# Dicio_bkup.net
KiCad netlist of a schematic drawn in EAGLE
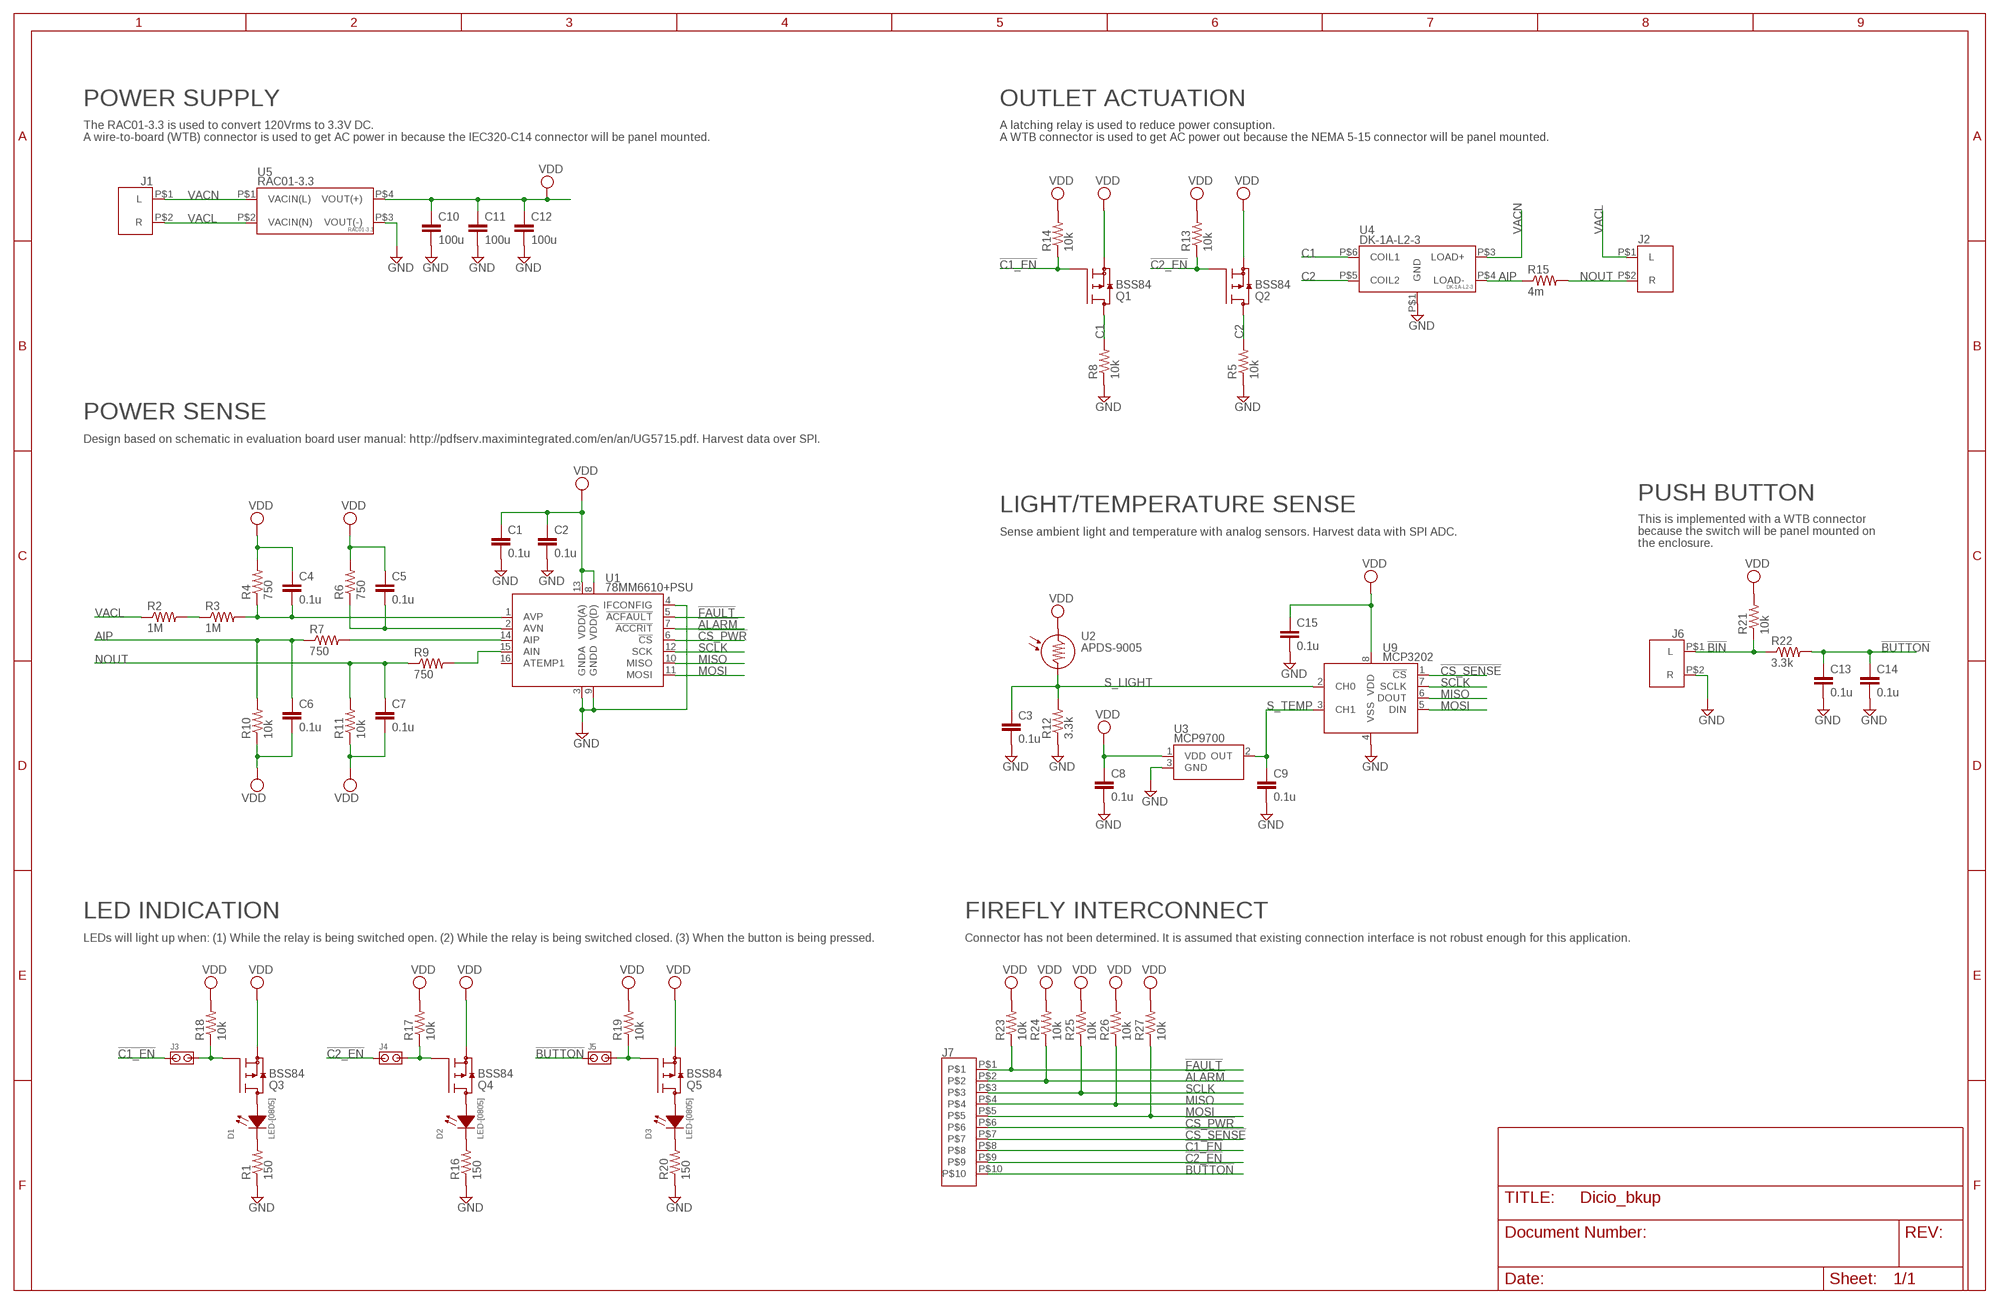
[diagram p0: schematic, sheet 1]

(export (version "E")
  (design (tool "Eeschema 10.0.6"))
  (components
    (comp (ref "C1")
      (value "0.1u")
      (footprint "eagle-import:C0805")
      (libsource (lib "eagle-import") (part "C-EUC0805"))
    )
    (comp (ref "C2")
      (value "0.1u")
      (footprint "eagle-import:C0805")
      (libsource (lib "eagle-import") (part "C-EUC0805"))
    )
    (comp (ref "C3")
      (value "0.1u")
      (footprint "eagle-import:C0805")
      (libsource (lib "eagle-import") (part "C-EUC0805"))
    )
    (comp (ref "C4")
      (value "0.1u")
      (footprint "eagle-import:C0805")
      (libsource (lib "eagle-import") (part "C-EUC0805"))
    )
    (comp (ref "C5")
      (value "0.1u")
      (footprint "eagle-import:C0805")
      (libsource (lib "eagle-import") (part "C-EUC0805"))
    )
    (comp (ref "C6")
      (value "0.1u")
      (footprint "eagle-import:C0805")
      (libsource (lib "eagle-import") (part "C-EUC0805"))
    )
    (comp (ref "C7")
      (value "0.1u")
      (footprint "eagle-import:C0805")
      (libsource (lib "eagle-import") (part "C-EUC0805"))
    )
    (comp (ref "C8")
      (value "0.1u")
      (footprint "eagle-import:C0805")
      (libsource (lib "eagle-import") (part "C-EUC0805"))
    )
    (comp (ref "C9")
      (value "0.1u")
      (footprint "eagle-import:C0805")
      (libsource (lib "eagle-import") (part "C-EUC0805"))
    )
    (comp (ref "C10")
      (value "100u")
      (footprint "eagle-import:C1206")
      (libsource (lib "eagle-import") (part "C-EUC1206"))
    )
    (comp (ref "C11")
      (value "100u")
      (footprint "eagle-import:C1206")
      (libsource (lib "eagle-import") (part "C-EUC1206"))
    )
    (comp (ref "C12")
      (value "100u")
      (footprint "eagle-import:C1206")
      (libsource (lib "eagle-import") (part "C-EUC1206"))
    )
    (comp (ref "C13")
      (value "0.1u")
      (footprint "eagle-import:C0805")
      (libsource (lib "eagle-import") (part "C-EUC0805"))
    )
    (comp (ref "C14")
      (value "0.1u")
      (footprint "eagle-import:C0805")
      (libsource (lib "eagle-import") (part "C-EUC0805"))
    )
    (comp (ref "C15")
      (value "0.1u")
      (footprint "eagle-import:C0805")
      (libsource (lib "eagle-import") (part "C-EUC0805"))
    )
    (comp (ref "D1")
      (value "LED-[0805]")
      (footprint "eagle-import:L0805")
      (libsource (lib "eagle-import") (part "LED-[0805]"))
    )
    (comp (ref "D2")
      (value "LED-[0805]")
      (footprint "eagle-import:L0805")
      (libsource (lib "eagle-import") (part "LED-[0805]"))
    )
    (comp (ref "D3")
      (value "LED-[0805]")
      (footprint "eagle-import:L0805")
      (libsource (lib "eagle-import") (part "LED-[0805]"))
    )
    (comp (ref "J1")
      (value "WTB-2")
      (footprint "eagle-import:[TERM][2][0.2]")
      (libsource (lib "eagle-import") (part "WTB-2"))
    )
    (comp (ref "J2")
      (value "WTB-2")
      (footprint "eagle-import:[TERM][2][0.2]")
      (libsource (lib "eagle-import") (part "WTB-2"))
    )
    (comp (ref "J3")
      (value "JMP2")
      (footprint "eagle-import:JMP2")
      (libsource (lib "eagle-import") (part "JMP2"))
    )
    (comp (ref "J4")
      (value "JMP2")
      (footprint "eagle-import:JMP2")
      (libsource (lib "eagle-import") (part "JMP2"))
    )
    (comp (ref "J5")
      (value "JMP2")
      (footprint "eagle-import:JMP2")
      (libsource (lib "eagle-import") (part "JMP2"))
    )
    (comp (ref "J6")
      (value "WTB-2")
      (footprint "eagle-import:[TERM][2][0.2]")
      (libsource (lib "eagle-import") (part "WTB-2"))
    )
    (comp (ref "J7")
      (value "TERM10")
      (footprint "eagle-import:TERM10")
      (libsource (lib "eagle-import") (part "TERM10"))
    )
    (comp (ref "Q1")
      (value "BSS84")
      (footprint "eagle-import:SOT23")
      (libsource (lib "eagle-import") (part "BSS84"))
    )
    (comp (ref "Q2")
      (value "BSS84")
      (footprint "eagle-import:SOT23")
      (libsource (lib "eagle-import") (part "BSS84"))
    )
    (comp (ref "Q3")
      (value "BSS84")
      (footprint "eagle-import:SOT23")
      (libsource (lib "eagle-import") (part "BSS84"))
    )
    (comp (ref "Q4")
      (value "BSS84")
      (footprint "eagle-import:SOT23")
      (libsource (lib "eagle-import") (part "BSS84"))
    )
    (comp (ref "Q5")
      (value "BSS84")
      (footprint "eagle-import:SOT23")
      (libsource (lib "eagle-import") (part "BSS84"))
    )
    (comp (ref "R1")
      (value "150")
      (footprint "eagle-import:R0805")
      (libsource (lib "eagle-import") (part "R-US_R0805"))
    )
    (comp (ref "R2")
      (value "1M")
      (footprint "eagle-import:R0805")
      (libsource (lib "eagle-import") (part "R-US_R0805"))
    )
    (comp (ref "R3")
      (value "1M")
      (footprint "eagle-import:R0805")
      (libsource (lib "eagle-import") (part "R-US_R0805"))
    )
    (comp (ref "R4")
      (value "750")
      (footprint "eagle-import:R0805")
      (libsource (lib "eagle-import") (part "R-US_R0805"))
    )
    (comp (ref "R5")
      (value "10k")
      (footprint "eagle-import:R0805")
      (libsource (lib "eagle-import") (part "R-US_R0805"))
    )
    (comp (ref "R6")
      (value "750")
      (footprint "eagle-import:R0805")
      (libsource (lib "eagle-import") (part "R-US_R0805"))
    )
    (comp (ref "R7")
      (value "750")
      (footprint "eagle-import:R0805")
      (libsource (lib "eagle-import") (part "R-US_R0805"))
    )
    (comp (ref "R8")
      (value "10k")
      (footprint "eagle-import:R0805")
      (libsource (lib "eagle-import") (part "R-US_R0805"))
    )
    (comp (ref "R9")
      (value "750")
      (footprint "eagle-import:R0805")
      (libsource (lib "eagle-import") (part "R-US_R0805"))
    )
    (comp (ref "R10")
      (value "10k")
      (footprint "eagle-import:R0805")
      (libsource (lib "eagle-import") (part "R-US_R0805"))
    )
    (comp (ref "R11")
      (value "10k")
      (footprint "eagle-import:R0805")
      (libsource (lib "eagle-import") (part "R-US_R0805"))
    )
    (comp (ref "R12")
      (value "3.3k")
      (footprint "eagle-import:R0805")
      (libsource (lib "eagle-import") (part "R-US_R0805"))
    )
    (comp (ref "R13")
      (value "10k")
      (footprint "eagle-import:R0805")
      (libsource (lib "eagle-import") (part "R-US_R0805"))
    )
    (comp (ref "R14")
      (value "10k")
      (footprint "eagle-import:R0805")
      (libsource (lib "eagle-import") (part "R-US_R0805"))
    )
    (comp (ref "R15")
      (value "4m")
      (footprint "eagle-import:R2512")
      (libsource (lib "eagle-import") (part "R-US_R2512"))
    )
    (comp (ref "R16")
      (value "150")
      (footprint "eagle-import:R0805")
      (libsource (lib "eagle-import") (part "R-US_R0805"))
    )
    (comp (ref "R17")
      (value "10k")
      (footprint "eagle-import:R0805")
      (libsource (lib "eagle-import") (part "R-US_R0805"))
    )
    (comp (ref "R18")
      (value "10k")
      (footprint "eagle-import:R0805")
      (libsource (lib "eagle-import") (part "R-US_R0805"))
    )
    (comp (ref "R19")
      (value "10k")
      (footprint "eagle-import:R0805")
      (libsource (lib "eagle-import") (part "R-US_R0805"))
    )
    (comp (ref "R20")
      (value "150")
      (footprint "eagle-import:R0805")
      (libsource (lib "eagle-import") (part "R-US_R0805"))
    )
    (comp (ref "R21")
      (value "10k")
      (footprint "eagle-import:R0805")
      (libsource (lib "eagle-import") (part "R-US_R0805"))
    )
    (comp (ref "R22")
      (value "3.3k")
      (footprint "eagle-import:R0805")
      (libsource (lib "eagle-import") (part "R-US_R0805"))
    )
    (comp (ref "R23")
      (value "10k")
      (footprint "eagle-import:R0805")
      (libsource (lib "eagle-import") (part "R-US_R0805"))
    )
    (comp (ref "R24")
      (value "10k")
      (footprint "eagle-import:R0805")
      (libsource (lib "eagle-import") (part "R-US_R0805"))
    )
    (comp (ref "R25")
      (value "10k")
      (footprint "eagle-import:R0805")
      (libsource (lib "eagle-import") (part "R-US_R0805"))
    )
    (comp (ref "R26")
      (value "10k")
      (footprint "eagle-import:R0805")
      (libsource (lib "eagle-import") (part "R-US_R0805"))
    )
    (comp (ref "R27")
      (value "10k")
      (footprint "eagle-import:R0805")
      (libsource (lib "eagle-import") (part "R-US_R0805"))
    )
    (comp (ref "U1")
      (value "78MM6610+PSU")
      (footprint "eagle-import:TSSOP16")
      (libsource (lib "eagle-import") (part "78MM6610+PSU"))
    )
    (comp (ref "U2")
      (value "APDS-9005")
      (footprint "eagle-import:APDS-9005")
      (libsource (lib "eagle-import") (part "APDS-9005"))
    )
    (comp (ref "U3")
      (value "MCP9700")
      (footprint "eagle-import:SOT23")
      (libsource (lib "eagle-import") (part "MCP9700"))
    )
    (comp (ref "U4")
      (value "DK-1A-L2-3")
      (footprint "eagle-import:DK-1A-L2-3")
      (libsource (lib "eagle-import") (part "DK-1A-L2-3"))
    )
    (comp (ref "U5")
      (value "RAC01-3.3")
      (footprint "eagle-import:RAC01-3.3")
      (libsource (lib "eagle-import") (part "RAC01-3.3"))
    )
    (comp (ref "U9")
      (value "MCP3202")
      (footprint "eagle-import:MSOP-8[MCP3202]")
      (libsource (lib "eagle-import") (part "MCP3202"))
    )
  )
  (nets
    (net (code "1") (name "/AIP") (class "Default")
      (node (ref "C6") (pin "1") (pinfunction "1_1") (pintype "passive"))
      (node (ref "R10") (pin "2") (pinfunction "2_2") (pintype "passive"))
      (node (ref "R15") (pin "1") (pinfunction "1_1") (pintype "passive"))
      (node (ref "R7") (pin "1") (pinfunction "1_1") (pintype "passive"))
      (node (ref "U4") (pin "P$4") (pinfunction "LOAD-_P$4") (pintype "bidirectional"))
    )
    (net (code "2") (name "/C1") (class "Default")
      (node (ref "Q1") (pin "3") (pinfunction "D_3") (pintype "bidirectional"))
      (node (ref "R8") (pin "2") (pinfunction "2_2") (pintype "passive"))
      (node (ref "U4") (pin "P$6") (pinfunction "COIL1_P$6") (pintype "bidirectional"))
    )
    (net (code "3") (name "/C2") (class "Default")
      (node (ref "Q2") (pin "3") (pinfunction "D_3") (pintype "bidirectional"))
      (node (ref "R5") (pin "2") (pinfunction "2_2") (pintype "passive"))
      (node (ref "U4") (pin "P$5") (pinfunction "COIL2_P$5") (pintype "bidirectional"))
    )
    (net (code "4") (name "/MISO") (class "Default")
      (node (ref "J7") (pin "P$4") (pinfunction "P$4_P$4") (pintype "bidirectional"))
      (node (ref "R26") (pin "1") (pinfunction "1_1") (pintype "passive"))
      (node (ref "U1") (pin "10") (pinfunction "MISO_10") (pintype "bidirectional"))
      (node (ref "U9") (pin "6") (pinfunction "DOUT_6") (pintype "bidirectional"))
    )
    (net (code "5") (name "/MOSI") (class "Default")
      (node (ref "J7") (pin "P$5") (pinfunction "P$5_P$5") (pintype "bidirectional"))
      (node (ref "R27") (pin "1") (pinfunction "1_1") (pintype "passive"))
      (node (ref "U1") (pin "11") (pinfunction "MOSI_11") (pintype "bidirectional"))
      (node (ref "U9") (pin "5") (pinfunction "DIN_5") (pintype "bidirectional"))
    )
    (net (code "6") (name "/NOUT") (class "Default")
      (node (ref "C7") (pin "1") (pinfunction "1_1") (pintype "passive"))
      (node (ref "J2") (pin "P$2") (pinfunction "R_P$2") (pintype "bidirectional"))
      (node (ref "R11") (pin "2") (pinfunction "2_2") (pintype "passive"))
      (node (ref "R15") (pin "2") (pinfunction "2_2") (pintype "passive"))
      (node (ref "R9") (pin "1") (pinfunction "1_1") (pintype "passive"))
    )
    (net (code "7") (name "/SCLK") (class "Default")
      (node (ref "J7") (pin "P$3") (pinfunction "P$3_P$3") (pintype "bidirectional"))
      (node (ref "R25") (pin "1") (pinfunction "1_1") (pintype "passive"))
      (node (ref "U1") (pin "12") (pinfunction "SCK_12") (pintype "bidirectional"))
      (node (ref "U9") (pin "7") (pinfunction "SCLK_7") (pintype "bidirectional"))
    )
    (net (code "8") (name "/S_LIGHT") (class "Default")
      (node (ref "C3") (pin "1") (pinfunction "1_1") (pintype "passive"))
      (node (ref "R12") (pin "2") (pinfunction "2_2") (pintype "passive"))
      (node (ref "U2") (pin "6") (pinfunction "ROUT_6") (pintype "bidirectional"))
      (node (ref "U9") (pin "2") (pinfunction "CH0_2") (pintype "bidirectional"))
    )
    (net (code "9") (name "/S_TEMP") (class "Default")
      (node (ref "C9") (pin "1") (pinfunction "1_1") (pintype "passive"))
      (node (ref "U3") (pin "2") (pinfunction "OUT_2") (pintype "bidirectional"))
      (node (ref "U9") (pin "3") (pinfunction "CH1_3") (pintype "bidirectional"))
    )
    (net (code "10") (name "/VACL") (class "Default")
      (node (ref "J1") (pin "P$2") (pinfunction "R_P$2") (pintype "bidirectional"))
      (node (ref "J2") (pin "P$1") (pinfunction "L_P$1") (pintype "bidirectional"))
      (node (ref "R2") (pin "1") (pinfunction "1_1") (pintype "passive"))
      (node (ref "U5") (pin "P$2") (pinfunction "VACIN(N)_P$2") (pintype "bidirectional"))
    )
    (net (code "11") (name "/VACN") (class "Default")
      (node (ref "J1") (pin "P$1") (pinfunction "L_P$1") (pintype "bidirectional"))
      (node (ref "U4") (pin "P$3") (pinfunction "LOAD+_P$3") (pintype "bidirectional"))
      (node (ref "U5") (pin "P$1") (pinfunction "VACIN(L)_P$1") (pintype "bidirectional"))
    )
    (net (code "12") (name "/~{ALARM}") (class "Default")
      (node (ref "J7") (pin "P$2") (pinfunction "P$2_P$2") (pintype "bidirectional"))
      (node (ref "R24") (pin "1") (pinfunction "1_1") (pintype "passive"))
      (node (ref "U1") (pin "7") (pinfunction "~{ACCRIT}_7") (pintype "bidirectional"))
    )
    (net (code "13") (name "/~{BIN}") (class "Default")
      (node (ref "J6") (pin "P$1") (pinfunction "L_P$1") (pintype "bidirectional"))
      (node (ref "R21") (pin "1") (pinfunction "1_1") (pintype "passive"))
      (node (ref "R22") (pin "1") (pinfunction "1_1") (pintype "passive"))
    )
    (net (code "14") (name "/~{BUTTON}") (class "Default")
      (node (ref "C13") (pin "1") (pinfunction "1_1") (pintype "passive"))
      (node (ref "C14") (pin "1") (pinfunction "1_1") (pintype "passive"))
      (node (ref "J5") (pin "P$2") (pinfunction "P$2_P$2") (pintype "bidirectional"))
      (node (ref "J7") (pin "P$10") (pinfunction "P$10_P$10") (pintype "bidirectional"))
      (node (ref "R22") (pin "2") (pinfunction "2_2") (pintype "passive"))
    )
    (net (code "15") (name "/~{C1_EN}") (class "Default")
      (node (ref "J3") (pin "P$2") (pinfunction "P$2_P$2") (pintype "bidirectional"))
      (node (ref "J7") (pin "P$8") (pinfunction "P$8_P$8") (pintype "bidirectional"))
      (node (ref "Q1") (pin "1") (pinfunction "G_1") (pintype "bidirectional"))
      (node (ref "R14") (pin "1") (pinfunction "1_1") (pintype "passive"))
    )
    (net (code "16") (name "/~{C2_EN}") (class "Default")
      (node (ref "J4") (pin "P$2") (pinfunction "P$2_P$2") (pintype "bidirectional"))
      (node (ref "J7") (pin "P$9") (pinfunction "P$9_P$9") (pintype "bidirectional"))
      (node (ref "Q2") (pin "1") (pinfunction "G_1") (pintype "bidirectional"))
      (node (ref "R13") (pin "1") (pinfunction "1_1") (pintype "passive"))
    )
    (net (code "17") (name "/~{CS_PWR}") (class "Default")
      (node (ref "J7") (pin "P$6") (pinfunction "P$6_P$6") (pintype "bidirectional"))
      (node (ref "U1") (pin "6") (pinfunction "~{CS}_6") (pintype "bidirectional"))
    )
    (net (code "18") (name "/~{CS_SENSE}") (class "Default")
      (node (ref "J7") (pin "P$7") (pinfunction "P$7_P$7") (pintype "bidirectional"))
      (node (ref "U9") (pin "1") (pinfunction "~{CS}_1") (pintype "bidirectional"))
    )
    (net (code "19") (name "/~{FAULT}") (class "Default")
      (node (ref "J7") (pin "P$1") (pinfunction "P$1_P$1") (pintype "bidirectional"))
      (node (ref "R23") (pin "1") (pinfunction "1_1") (pintype "passive"))
      (node (ref "U1") (pin "5") (pinfunction "~{ACFAULT}_5") (pintype "bidirectional"))
    )
    (net (code "20") (name "GND") (class "Default")
      (node (ref "C1") (pin "2") (pinfunction "2_2") (pintype "passive"))
      (node (ref "C10") (pin "2") (pinfunction "2_2") (pintype "passive"))
      (node (ref "C11") (pin "2") (pinfunction "2_2") (pintype "passive"))
      (node (ref "C12") (pin "2") (pinfunction "2_2") (pintype "passive"))
      (node (ref "C13") (pin "2") (pinfunction "2_2") (pintype "passive"))
      (node (ref "C14") (pin "2") (pinfunction "2_2") (pintype "passive"))
      (node (ref "C15") (pin "2") (pinfunction "2_2") (pintype "passive"))
      (node (ref "C2") (pin "2") (pinfunction "2_2") (pintype "passive"))
      (node (ref "C3") (pin "2") (pinfunction "2_2") (pintype "passive"))
      (node (ref "C8") (pin "2") (pinfunction "2_2") (pintype "passive"))
      (node (ref "C9") (pin "2") (pinfunction "2_2") (pintype "passive"))
      (node (ref "J6") (pin "P$2") (pinfunction "R_P$2") (pintype "bidirectional"))
      (node (ref "R1") (pin "1") (pinfunction "1_1") (pintype "passive"))
      (node (ref "R12") (pin "1") (pinfunction "1_1") (pintype "passive"))
      (node (ref "R16") (pin "1") (pinfunction "1_1") (pintype "passive"))
      (node (ref "R20") (pin "1") (pinfunction "1_1") (pintype "passive"))
      (node (ref "R5") (pin "1") (pinfunction "1_1") (pintype "passive"))
      (node (ref "R8") (pin "1") (pinfunction "1_1") (pintype "passive"))
      (node (ref "U1") (pin "3") (pinfunction "GNDA_3") (pintype "bidirectional"))
      (node (ref "U1") (pin "4") (pinfunction "IFCONFIG_4") (pintype "bidirectional"))
      (node (ref "U1") (pin "9") (pinfunction "GNDD_9") (pintype "bidirectional"))
      (node (ref "U3") (pin "3") (pinfunction "GND_3") (pintype "bidirectional"))
      (node (ref "U4") (pin "P$1") (pinfunction "GND_P$1") (pintype "bidirectional"))
      (node (ref "U5") (pin "P$3") (pinfunction "VOUT(-)_P$3") (pintype "bidirectional"))
      (node (ref "U9") (pin "4") (pinfunction "VSS_4") (pintype "bidirectional"))
    )
    (net (code "21") (name "Net-(D1-A)") (class "Default")
      (node (ref "D1") (pin "1") (pinfunction "A_1") (pintype "bidirectional"))
      (node (ref "Q3") (pin "3") (pinfunction "D_3") (pintype "bidirectional"))
    )
    (net (code "22") (name "Net-(D1-C)") (class "Default")
      (node (ref "D1") (pin "2") (pinfunction "C_2") (pintype "bidirectional"))
      (node (ref "R1") (pin "2") (pinfunction "2_2") (pintype "passive"))
    )
    (net (code "23") (name "Net-(D2-A)") (class "Default")
      (node (ref "D2") (pin "1") (pinfunction "A_1") (pintype "bidirectional"))
      (node (ref "Q4") (pin "3") (pinfunction "D_3") (pintype "bidirectional"))
    )
    (net (code "24") (name "Net-(D2-C)") (class "Default")
      (node (ref "D2") (pin "2") (pinfunction "C_2") (pintype "bidirectional"))
      (node (ref "R16") (pin "2") (pinfunction "2_2") (pintype "passive"))
    )
    (net (code "25") (name "Net-(D3-A)") (class "Default")
      (node (ref "D3") (pin "1") (pinfunction "A_1") (pintype "bidirectional"))
      (node (ref "Q5") (pin "3") (pinfunction "D_3") (pintype "bidirectional"))
    )
    (net (code "26") (name "Net-(D3-C)") (class "Default")
      (node (ref "D3") (pin "2") (pinfunction "C_2") (pintype "bidirectional"))
      (node (ref "R20") (pin "2") (pinfunction "2_2") (pintype "passive"))
    )
    (net (code "27") (name "Net-(J3-1)") (class "Default")
      (node (ref "J3") (pin "P$1") (pinfunction "1_P$1") (pintype "bidirectional"))
      (node (ref "Q3") (pin "1") (pinfunction "G_1") (pintype "bidirectional"))
      (node (ref "R18") (pin "1") (pinfunction "1_1") (pintype "passive"))
    )
    (net (code "28") (name "Net-(J4-1)") (class "Default")
      (node (ref "J4") (pin "P$1") (pinfunction "1_P$1") (pintype "bidirectional"))
      (node (ref "Q4") (pin "1") (pinfunction "G_1") (pintype "bidirectional"))
      (node (ref "R17") (pin "1") (pinfunction "1_1") (pintype "passive"))
    )
    (net (code "29") (name "Net-(J5-1)") (class "Default")
      (node (ref "J5") (pin "P$1") (pinfunction "1_P$1") (pintype "bidirectional"))
      (node (ref "Q5") (pin "1") (pinfunction "G_1") (pintype "bidirectional"))
      (node (ref "R19") (pin "1") (pinfunction "1_1") (pintype "passive"))
    )
    (net (code "30") (name "Net-(R2-Pad2)") (class "Default")
      (node (ref "R2") (pin "2") (pinfunction "2_2") (pintype "passive"))
      (node (ref "R3") (pin "1") (pinfunction "1_1") (pintype "passive"))
    )
    (net (code "31") (name "Net-(U1-AIN)") (class "Default")
      (node (ref "R9") (pin "2") (pinfunction "2_2") (pintype "passive"))
      (node (ref "U1") (pin "15") (pinfunction "AIN_15") (pintype "bidirectional"))
    )
    (net (code "32") (name "Net-(U1-AIP)") (class "Default")
      (node (ref "R7") (pin "2") (pinfunction "2_2") (pintype "passive"))
      (node (ref "U1") (pin "14") (pinfunction "AIP_14") (pintype "bidirectional"))
    )
    (net (code "33") (name "Net-(U1-AVN)") (class "Default")
      (node (ref "C5") (pin "2") (pinfunction "2_2") (pintype "passive"))
      (node (ref "R6") (pin "1") (pinfunction "1_1") (pintype "passive"))
      (node (ref "U1") (pin "2") (pinfunction "AVN_2") (pintype "bidirectional"))
    )
    (net (code "34") (name "Net-(U1-AVP)") (class "Default")
      (node (ref "C4") (pin "2") (pinfunction "2_2") (pintype "passive"))
      (node (ref "R3") (pin "2") (pinfunction "2_2") (pintype "passive"))
      (node (ref "R4") (pin "1") (pinfunction "1_1") (pintype "passive"))
      (node (ref "U1") (pin "1") (pinfunction "AVP_1") (pintype "bidirectional"))
    )
    (net (code "35") (name "VDD") (class "Default")
      (node (ref "C1") (pin "1") (pinfunction "1_1") (pintype "passive"))
      (node (ref "C10") (pin "1") (pinfunction "1_1") (pintype "passive"))
      (node (ref "C11") (pin "1") (pinfunction "1_1") (pintype "passive"))
      (node (ref "C12") (pin "1") (pinfunction "1_1") (pintype "passive"))
      (node (ref "C15") (pin "1") (pinfunction "1_1") (pintype "passive"))
      (node (ref "C2") (pin "1") (pinfunction "1_1") (pintype "passive"))
      (node (ref "C4") (pin "1") (pinfunction "1_1") (pintype "passive"))
      (node (ref "C5") (pin "1") (pinfunction "1_1") (pintype "passive"))
      (node (ref "C6") (pin "2") (pinfunction "2_2") (pintype "passive"))
      (node (ref "C7") (pin "2") (pinfunction "2_2") (pintype "passive"))
      (node (ref "C8") (pin "1") (pinfunction "1_1") (pintype "passive"))
      (node (ref "Q1") (pin "2") (pinfunction "S_2") (pintype "bidirectional"))
      (node (ref "Q2") (pin "2") (pinfunction "S_2") (pintype "bidirectional"))
      (node (ref "Q3") (pin "2") (pinfunction "S_2") (pintype "bidirectional"))
      (node (ref "Q4") (pin "2") (pinfunction "S_2") (pintype "bidirectional"))
      (node (ref "Q5") (pin "2") (pinfunction "S_2") (pintype "bidirectional"))
      (node (ref "R10") (pin "1") (pinfunction "1_1") (pintype "passive"))
      (node (ref "R11") (pin "1") (pinfunction "1_1") (pintype "passive"))
      (node (ref "R13") (pin "2") (pinfunction "2_2") (pintype "passive"))
      (node (ref "R14") (pin "2") (pinfunction "2_2") (pintype "passive"))
      (node (ref "R17") (pin "2") (pinfunction "2_2") (pintype "passive"))
      (node (ref "R18") (pin "2") (pinfunction "2_2") (pintype "passive"))
      (node (ref "R19") (pin "2") (pinfunction "2_2") (pintype "passive"))
      (node (ref "R21") (pin "2") (pinfunction "2_2") (pintype "passive"))
      (node (ref "R23") (pin "2") (pinfunction "2_2") (pintype "passive"))
      (node (ref "R24") (pin "2") (pinfunction "2_2") (pintype "passive"))
      (node (ref "R25") (pin "2") (pinfunction "2_2") (pintype "passive"))
      (node (ref "R26") (pin "2") (pinfunction "2_2") (pintype "passive"))
      (node (ref "R27") (pin "2") (pinfunction "2_2") (pintype "passive"))
      (node (ref "R4") (pin "2") (pinfunction "2_2") (pintype "passive"))
      (node (ref "R6") (pin "2") (pinfunction "2_2") (pintype "passive"))
      (node (ref "U1") (pin "13") (pinfunction "VDD(A)_13") (pintype "bidirectional"))
      (node (ref "U1") (pin "8") (pinfunction "VDD(D)_8") (pintype "bidirectional"))
      (node (ref "U2") (pin "1") (pinfunction "VDD_1") (pintype "bidirectional"))
      (node (ref "U3") (pin "1") (pinfunction "VDD_1") (pintype "bidirectional"))
      (node (ref "U5") (pin "P$4") (pinfunction "VOUT(+)_P$4") (pintype "bidirectional"))
      (node (ref "U9") (pin "8") (pinfunction "VDD_8") (pintype "bidirectional"))
    )
    (net (code "36") (name "unconnected-(U1-ATEMP1-Pad16)") (class "Default")
      (node (ref "U1") (pin "16") (pinfunction "ATEMP1_16") (pintype "bidirectional"))
    )
    (net (code "37") (name "unconnected-(U2-NC1-Pad2)") (class "Default")
      (node (ref "U2") (pin "2") (pinfunction "NC1_2") (pintype "bidirectional"))
    )
    (net (code "38") (name "unconnected-(U2-NC2-Pad3)") (class "Default")
      (node (ref "U2") (pin "3") (pinfunction "NC2_3") (pintype "bidirectional"))
    )
    (net (code "39") (name "unconnected-(U2-NC3-Pad4)") (class "Default")
      (node (ref "U2") (pin "4") (pinfunction "NC3_4") (pintype "bidirectional"))
    )
    (net (code "40") (name "unconnected-(U2-NC4-Pad5)") (class "Default")
      (node (ref "U2") (pin "5") (pinfunction "NC4_5") (pintype "bidirectional"))
    )
  )
)
